# Motor_Driver_r1_1.net
KiCad netlist of a schematic drawn in Altium Designer
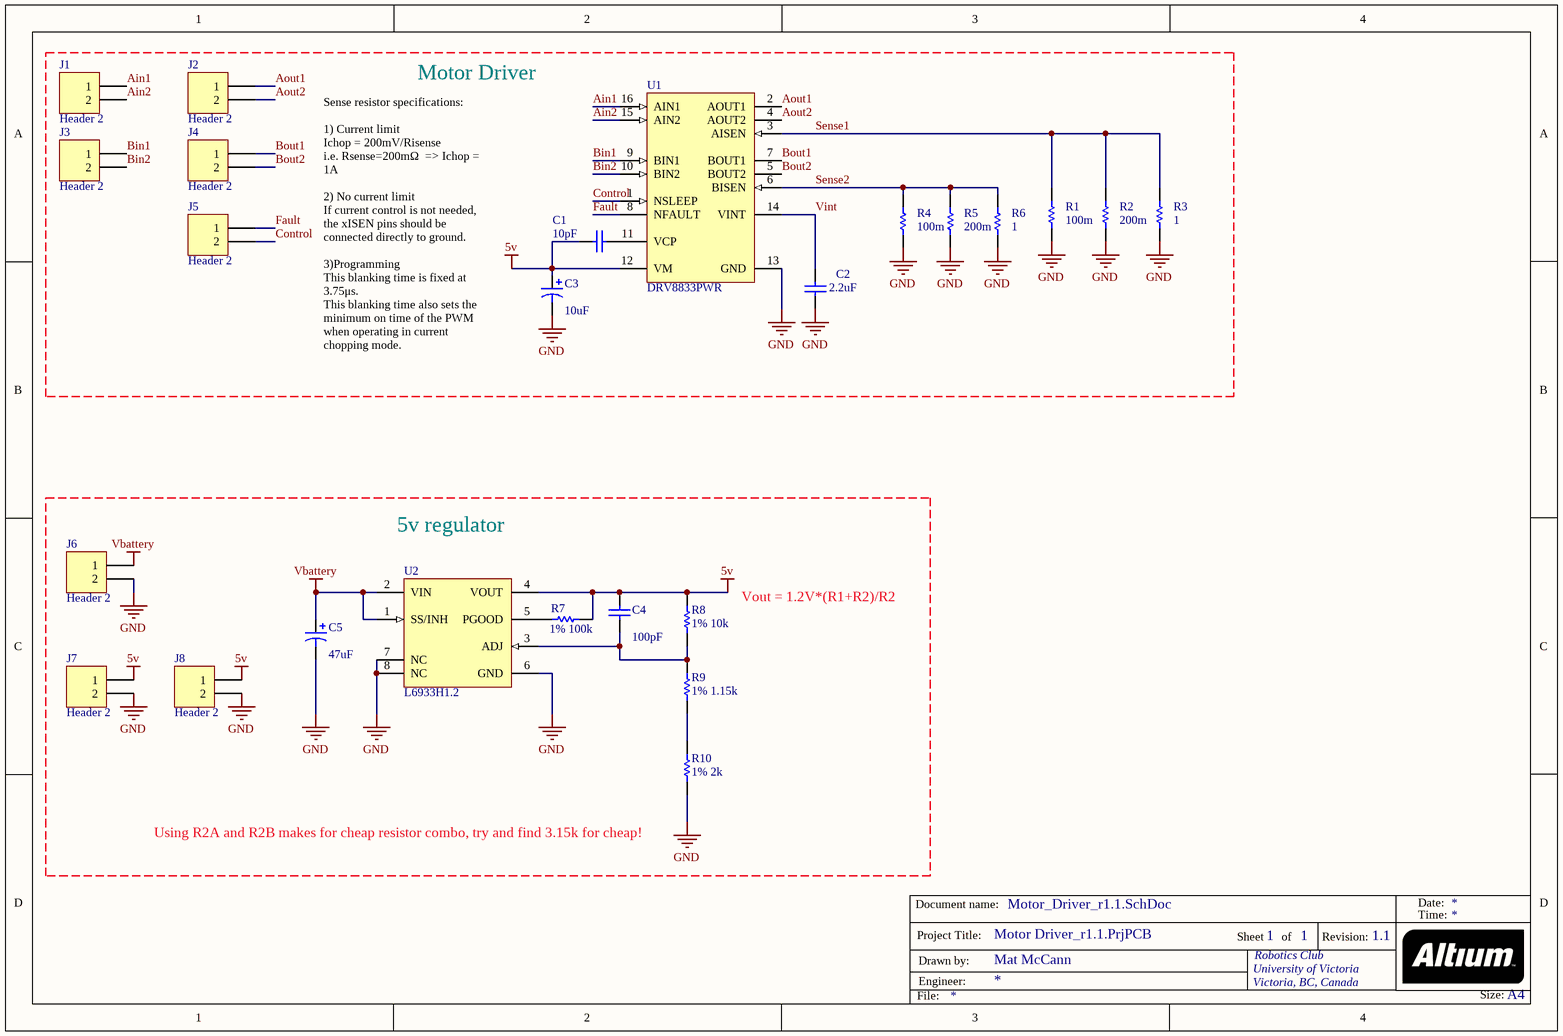
[diagram p0: Motor_Driver_r1.1.SchDoc]

(export (version "E")
  (design (tool "Eeschema 10.0.6"))
  (components
    (comp (ref "C1")
      (value "10pF")
      (footprint "6-0805_M")
      (description "Capacitor")
      (fields (field (name "Comment") "10pF cap"))
      (libsource (lib "Miscellaneous Devices") (part "Cap"))
    )
    (comp (ref "C2")
      (value "2.2uF")
      (footprint "6-0805_M")
      (description "Capacitor")
      (fields (field (name "Comment") "2.2uF cap"))
      (libsource (lib "Miscellaneous Devices") (part "Cap"))
    )
    (comp (ref "C3")
      (value "10uF")
      (footprint "CAP SMD")
      (description "Polarized Capacitor (Radial)")
      (libsource (lib "Miscellaneous Devices") (part "Cap Pol1"))
    )
    (comp (ref "C4")
      (value "100pF")
      (footprint "6-0805_M")
      (description "Capacitor")
      (fields (field (name "Comment") "100pF Cap"))
      (libsource (lib "Miscellaneous Devices") (part "Cap"))
    )
    (comp (ref "C5")
      (value "47uF")
      (footprint "capacitor_tantalum")
      (description "Polarized Capacitor (Radial)")
      (fields (field (name "Comment") "47uF Electrolytic"))
      (libsource (lib "Miscellaneous Devices") (part "Cap Pol1"))
    )
    (comp (ref "J1")
      (value "Header 2")
      (footprint "HDR1X2")
      (description "Header, 2-Pin")
      (libsource (lib "Miscellaneous Connectors") (part "Header 2"))
    )
    (comp (ref "J2")
      (value "Header 2")
      (footprint "HDR1X2")
      (description "Header, 2-Pin")
      (libsource (lib "Miscellaneous Connectors") (part "Header 2"))
    )
    (comp (ref "J3")
      (value "Header 2")
      (footprint "HDR1X2")
      (description "Header, 2-Pin")
      (libsource (lib "Miscellaneous Connectors") (part "Header 2"))
    )
    (comp (ref "J4")
      (value "Header 2")
      (footprint "HDR1X2")
      (description "Header, 2-Pin")
      (libsource (lib "Miscellaneous Connectors") (part "Header 2"))
    )
    (comp (ref "J5")
      (value "Header 2")
      (footprint "HDR1X2")
      (description "Header, 2-Pin")
      (libsource (lib "Miscellaneous Connectors") (part "Header 2"))
    )
    (comp (ref "J6")
      (value "Header 2")
      (footprint "HDR1X2")
      (description "Header, 2-Pin")
      (libsource (lib "Miscellaneous Connectors") (part "Header 2"))
    )
    (comp (ref "J7")
      (value "Header 2")
      (footprint "HDR1X2")
      (description "Header, 2-Pin")
      (libsource (lib "Miscellaneous Connectors") (part "Header 2"))
    )
    (comp (ref "J8")
      (value "Header 2")
      (footprint "HDR1X2")
      (description "Header, 2-Pin")
      (libsource (lib "Miscellaneous Connectors") (part "Header 2"))
    )
    (comp (ref "R1")
      (value "100m")
      (footprint "6-0805_M")
      (description "Resistor")
      (libsource (lib "Miscellaneous Devices") (part "Res1"))
    )
    (comp (ref "R2")
      (value "200m")
      (footprint "6-0805_M")
      (description "Resistor")
      (libsource (lib "Miscellaneous Devices") (part "Res1"))
    )
    (comp (ref "R3")
      (value "1")
      (footprint "6-0805_M")
      (description "Resistor")
      (libsource (lib "Miscellaneous Devices") (part "Res1"))
    )
    (comp (ref "R4")
      (value "100m")
      (footprint "6-0805_M")
      (description "Resistor")
      (libsource (lib "Miscellaneous Devices") (part "Res1"))
    )
    (comp (ref "R5")
      (value "200m")
      (footprint "6-0805_M")
      (description "Resistor")
      (libsource (lib "Miscellaneous Devices") (part "Res1"))
    )
    (comp (ref "R6")
      (value "1")
      (footprint "6-0805_M")
      (description "Resistor")
      (libsource (lib "Miscellaneous Devices") (part "Res1"))
    )
    (comp (ref "R7")
      (value "1% 100k")
      (footprint "6-0805_M")
      (description "Resistor")
      (libsource (lib "Miscellaneous Devices") (part "Res1"))
    )
    (comp (ref "R8")
      (value "1% 10k")
      (footprint "6-0805_M")
      (description "Resistor")
      (libsource (lib "Miscellaneous Devices") (part "Res1"))
    )
    (comp (ref "R9")
      (value "1% 1.15k")
      (footprint "6-0805_M")
      (description "Resistor")
      (libsource (lib "Miscellaneous Devices") (part "Res1"))
    )
    (comp (ref "R10")
      (value "1% 2k")
      (footprint "6-0805_M")
      (description "Resistor")
      (libsource (lib "Miscellaneous Devices") (part "Res1"))
    )
    (comp (ref "U1")
      (value "DRV8833PWR")
      (footprint "TI-PW16_M")
      (libsource (lib "Altium Content Vault") (part "CMP-1529-00001-1"))
    )
    (comp (ref "U2")
      (value "L6933H1.2")
      (footprint "SO8_M")
      (description "High Performance 2A ULDO Linear Regulator with Soft Start, 8-Pin SO")
      (libsource (lib "Altium Content Vault") (part "CMP-0240-00057-1"))
    )
  )
  (nets
    (net (code "1") (name "/Ain1") (class "Default")
      (node (ref "J1") (pin "1") (pinfunction "1_1") (pintype "passive"))
      (node (ref "U1") (pin "16") (pinfunction "AIN1_16") (pintype "input"))
    )
    (net (code "2") (name "/Ain2") (class "Default")
      (node (ref "J1") (pin "2") (pinfunction "2_2") (pintype "passive"))
      (node (ref "U1") (pin "15") (pinfunction "AIN2_15") (pintype "input"))
    )
    (net (code "3") (name "/Aout1") (class "Default")
      (node (ref "J2") (pin "1") (pinfunction "1_1") (pintype "passive"))
      (node (ref "U1") (pin "2") (pinfunction "AOUT1_2") (pintype "tri_state"))
    )
    (net (code "4") (name "/Aout2") (class "Default")
      (node (ref "J2") (pin "2") (pinfunction "2_2") (pintype "passive"))
      (node (ref "U1") (pin "4") (pinfunction "AOUT2_4") (pintype "tri_state"))
    )
    (net (code "5") (name "/Bin1") (class "Default")
      (node (ref "J3") (pin "1") (pinfunction "1_1") (pintype "passive"))
      (node (ref "U1") (pin "9") (pinfunction "BIN1_9") (pintype "input"))
    )
    (net (code "6") (name "/Bin2") (class "Default")
      (node (ref "J3") (pin "2") (pinfunction "2_2") (pintype "passive"))
      (node (ref "U1") (pin "10") (pinfunction "BIN2_10") (pintype "input"))
    )
    (net (code "7") (name "/Bout1") (class "Default")
      (node (ref "J4") (pin "1") (pinfunction "1_1") (pintype "passive"))
      (node (ref "U1") (pin "7") (pinfunction "BOUT1_7") (pintype "tri_state"))
    )
    (net (code "8") (name "/Bout2") (class "Default")
      (node (ref "J4") (pin "2") (pinfunction "2_2") (pintype "passive"))
      (node (ref "U1") (pin "5") (pinfunction "BOUT2_5") (pintype "tri_state"))
    )
    (net (code "9") (name "/Control") (class "Default")
      (node (ref "J5") (pin "2") (pinfunction "2_2") (pintype "passive"))
      (node (ref "U1") (pin "1") (pinfunction "NSLEEP_1") (pintype "input"))
    )
    (net (code "10") (name "/Fault") (class "Default")
      (node (ref "J5") (pin "1") (pinfunction "1_1") (pintype "passive"))
      (node (ref "U1") (pin "8") (pinfunction "NFAULT_8") (pintype "open_collector"))
    )
    (net (code "11") (name "/Sense1") (class "Default")
      (node (ref "R1") (pin "2") (pinfunction "2_2") (pintype "passive"))
      (node (ref "R2") (pin "2") (pinfunction "2_2") (pintype "passive"))
      (node (ref "R3") (pin "2") (pinfunction "2_2") (pintype "passive"))
      (node (ref "U1") (pin "3") (pinfunction "AISEN_3") (pintype "input"))
    )
    (net (code "12") (name "/Sense2") (class "Default")
      (node (ref "R4") (pin "2") (pinfunction "2_2") (pintype "passive"))
      (node (ref "R5") (pin "2") (pinfunction "2_2") (pintype "passive"))
      (node (ref "R6") (pin "2") (pinfunction "2_2") (pintype "passive"))
      (node (ref "U1") (pin "6") (pinfunction "BISEN_6") (pintype "input"))
    )
    (net (code "13") (name "/Vint") (class "Default")
      (node (ref "C2") (pin "2") (pinfunction "2_2") (pintype "passive"))
      (node (ref "U1") (pin "14") (pinfunction "VINT_14") (pintype "passive"))
    )
    (net (code "14") (name "5v") (class "Default")
      (node (ref "C1") (pin "2") (pinfunction "2_2") (pintype "passive"))
      (node (ref "C3") (pin "1") (pinfunction "1_1") (pintype "passive"))
      (node (ref "C4") (pin "2") (pinfunction "2_2") (pintype "passive"))
      (node (ref "J7") (pin "1") (pinfunction "1_1") (pintype "passive"))
      (node (ref "J8") (pin "1") (pinfunction "1_1") (pintype "passive"))
      (node (ref "R7") (pin "2") (pinfunction "2_2") (pintype "passive"))
      (node (ref "R8") (pin "2") (pinfunction "2_2") (pintype "passive"))
      (node (ref "U1") (pin "12") (pinfunction "VM_12") (pintype "power_in"))
      (node (ref "U2") (pin "4") (pinfunction "VOUT_4") (pintype "power_in"))
    )
    (net (code "15") (name "GND") (class "Default")
      (node (ref "C2") (pin "1") (pinfunction "1_1") (pintype "passive"))
      (node (ref "C3") (pin "2") (pinfunction "2_2") (pintype "passive"))
      (node (ref "C5") (pin "2") (pinfunction "2_2") (pintype "passive"))
      (node (ref "J6") (pin "2") (pinfunction "2_2") (pintype "passive"))
      (node (ref "J7") (pin "2") (pinfunction "2_2") (pintype "passive"))
      (node (ref "J8") (pin "2") (pinfunction "2_2") (pintype "passive"))
      (node (ref "R1") (pin "1") (pinfunction "1_1") (pintype "passive"))
      (node (ref "R10") (pin "1") (pinfunction "1_1") (pintype "passive"))
      (node (ref "R2") (pin "1") (pinfunction "1_1") (pintype "passive"))
      (node (ref "R3") (pin "1") (pinfunction "1_1") (pintype "passive"))
      (node (ref "R4") (pin "1") (pinfunction "1_1") (pintype "passive"))
      (node (ref "R5") (pin "1") (pinfunction "1_1") (pintype "passive"))
      (node (ref "R6") (pin "1") (pinfunction "1_1") (pintype "passive"))
      (node (ref "U1") (pin "13") (pinfunction "GND_13") (pintype "power_in"))
      (node (ref "U2") (pin "6") (pinfunction "GND_6") (pintype "power_in"))
      (node (ref "U2") (pin "7") (pinfunction "NC_7") (pintype "passive"))
      (node (ref "U2") (pin "8") (pinfunction "NC_8") (pintype "passive"))
    )
    (net (code "16") (name "Net-(R10-Pad2)") (class "Default")
      (node (ref "R10") (pin "2") (pinfunction "2_2") (pintype "passive"))
      (node (ref "R9") (pin "1") (pinfunction "1_1") (pintype "passive"))
    )
    (net (code "17") (name "Net-(U1-VCP)") (class "Default")
      (node (ref "C1") (pin "1") (pinfunction "1_1") (pintype "passive"))
      (node (ref "U1") (pin "11") (pinfunction "VCP_11") (pintype "passive"))
    )
    (net (code "18") (name "Net-(U2-ADJ)") (class "Default")
      (node (ref "C4") (pin "1") (pinfunction "1_1") (pintype "passive"))
      (node (ref "R8") (pin "1") (pinfunction "1_1") (pintype "passive"))
      (node (ref "R9") (pin "2") (pinfunction "2_2") (pintype "passive"))
      (node (ref "U2") (pin "3") (pinfunction "ADJ_3") (pintype "input"))
    )
    (net (code "19") (name "Net-(U2-PGOOD)") (class "Default")
      (node (ref "R7") (pin "1") (pinfunction "1_1") (pintype "passive"))
      (node (ref "U2") (pin "5") (pinfunction "PGOOD_5") (pintype "open_collector"))
    )
    (net (code "20") (name "Vbattery") (class "Default")
      (node (ref "C5") (pin "1") (pinfunction "1_1") (pintype "passive"))
      (node (ref "J6") (pin "1") (pinfunction "1_1") (pintype "passive"))
      (node (ref "U2") (pin "1") (pinfunction "SS/INH_1") (pintype "input"))
      (node (ref "U2") (pin "2") (pinfunction "VIN_2") (pintype "power_in"))
    )
  )
)
